# B166A.net
KiCad netlist of a schematic drawn in EAGLE
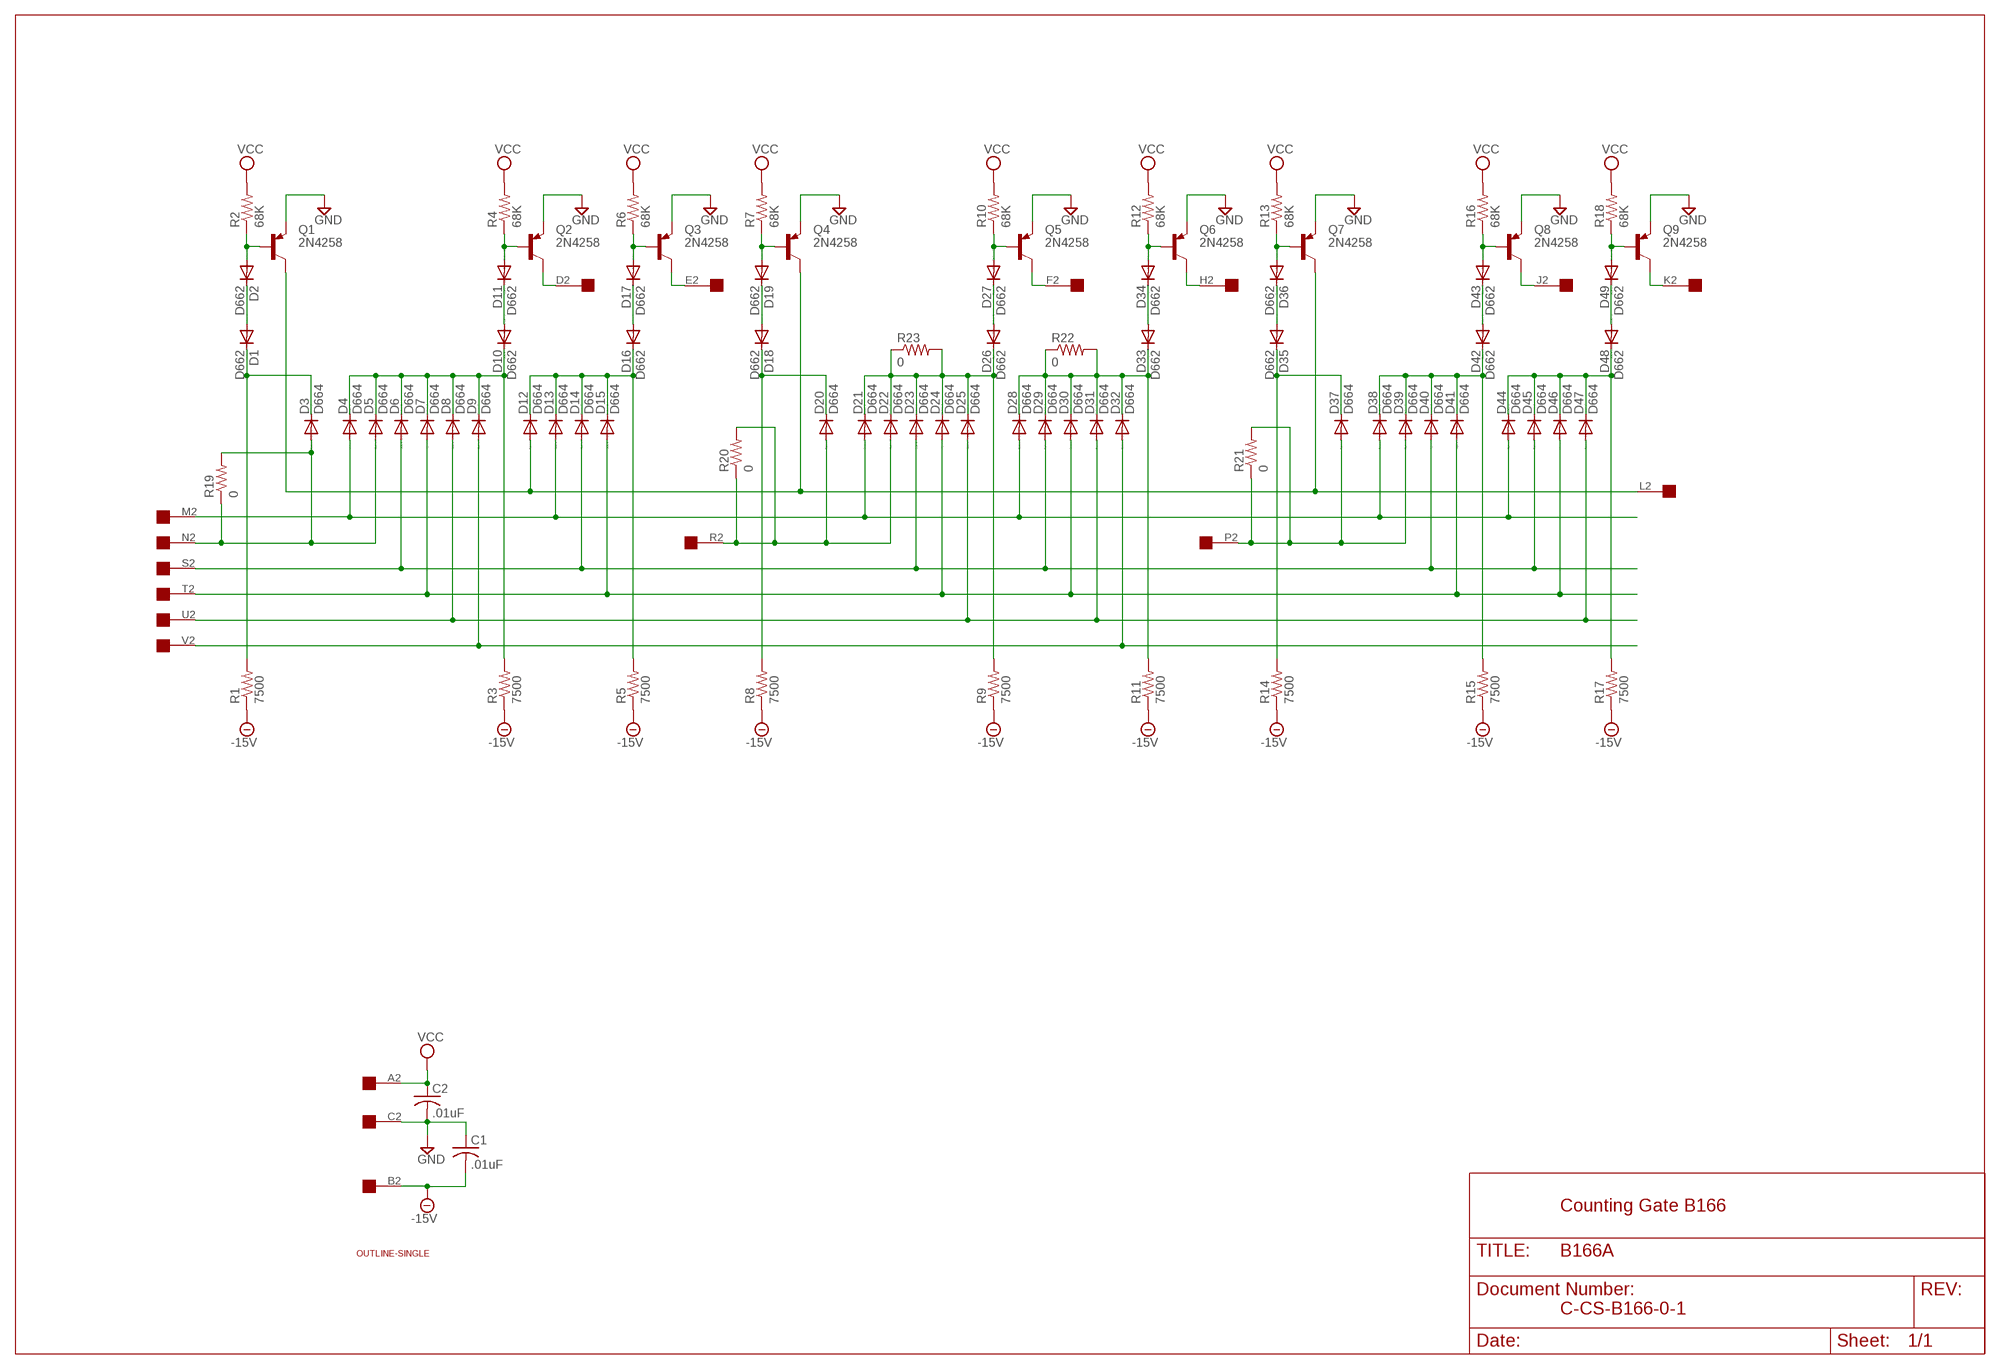
[diagram p0: schematic, sheet 1]

(export (version "E")
  (design (tool "Eeschema 10.0.6"))
  (components
    (comp (ref "C1")
      (value ".01uF")
      (footprint "eagle-import:C063-025X075")
      (libsource (lib "eagle-import") (part "C-US"))
    )
    (comp (ref "C2")
      (value ".01uF")
      (footprint "eagle-import:C063-025X075")
      (libsource (lib "eagle-import") (part "C-US"))
    )
    (comp (ref "D1")
      (value "D662")
      (footprint "eagle-import:DO35-10")
      (libsource (lib "eagle-import") (part "DIODE-DO35-10"))
    )
    (comp (ref "D2")
      (value "D662")
      (footprint "eagle-import:DO35-10")
      (libsource (lib "eagle-import") (part "DIODE-DO35-10"))
    )
    (comp (ref "D3")
      (value "D664")
      (footprint "eagle-import:DO35-10")
      (libsource (lib "eagle-import") (part "DIODE-DO35-10"))
    )
    (comp (ref "D4")
      (value "D664")
      (footprint "eagle-import:DO35-10")
      (libsource (lib "eagle-import") (part "DIODE-DO35-10"))
    )
    (comp (ref "D5")
      (value "D664")
      (footprint "eagle-import:DO35-10")
      (libsource (lib "eagle-import") (part "DIODE-DO35-10"))
    )
    (comp (ref "D6")
      (value "D664")
      (footprint "eagle-import:DO35-10")
      (libsource (lib "eagle-import") (part "DIODE-DO35-10"))
    )
    (comp (ref "D7")
      (value "D664")
      (footprint "eagle-import:DO35-10")
      (libsource (lib "eagle-import") (part "DIODE-DO35-10"))
    )
    (comp (ref "D8")
      (value "D664")
      (footprint "eagle-import:DO35-10")
      (libsource (lib "eagle-import") (part "DIODE-DO35-10"))
    )
    (comp (ref "D9")
      (value "D664")
      (footprint "eagle-import:DO35-10")
      (libsource (lib "eagle-import") (part "DIODE-DO35-10"))
    )
    (comp (ref "D10")
      (value "D662")
      (footprint "eagle-import:DO35-10")
      (libsource (lib "eagle-import") (part "DIODE-DO35-10"))
    )
    (comp (ref "D11")
      (value "D662")
      (footprint "eagle-import:DO35-10")
      (libsource (lib "eagle-import") (part "DIODE-DO35-10"))
    )
    (comp (ref "D12")
      (value "D664")
      (footprint "eagle-import:DO35-10")
      (libsource (lib "eagle-import") (part "DIODE-DO35-10"))
    )
    (comp (ref "D13")
      (value "D664")
      (footprint "eagle-import:DO35-10")
      (libsource (lib "eagle-import") (part "DIODE-DO35-10"))
    )
    (comp (ref "D14")
      (value "D664")
      (footprint "eagle-import:DO35-10")
      (libsource (lib "eagle-import") (part "DIODE-DO35-10"))
    )
    (comp (ref "D15")
      (value "D664")
      (footprint "eagle-import:DO35-10")
      (libsource (lib "eagle-import") (part "DIODE-DO35-10"))
    )
    (comp (ref "D16")
      (value "D662")
      (footprint "eagle-import:DO35-10")
      (libsource (lib "eagle-import") (part "DIODE-DO35-10"))
    )
    (comp (ref "D17")
      (value "D662")
      (footprint "eagle-import:DO35-10")
      (libsource (lib "eagle-import") (part "DIODE-DO35-10"))
    )
    (comp (ref "D18")
      (value "D662")
      (footprint "eagle-import:DO35-10")
      (libsource (lib "eagle-import") (part "DIODE-DO35-10"))
    )
    (comp (ref "D19")
      (value "D662")
      (footprint "eagle-import:DO35-10")
      (libsource (lib "eagle-import") (part "DIODE-DO35-10"))
    )
    (comp (ref "D20")
      (value "D664")
      (footprint "eagle-import:DO35-10")
      (libsource (lib "eagle-import") (part "DIODE-DO35-10"))
    )
    (comp (ref "D21")
      (value "D664")
      (footprint "eagle-import:DO35-10")
      (libsource (lib "eagle-import") (part "DIODE-DO35-10"))
    )
    (comp (ref "D22")
      (value "D664")
      (footprint "eagle-import:DO35-10")
      (libsource (lib "eagle-import") (part "DIODE-DO35-10"))
    )
    (comp (ref "D23")
      (value "D664")
      (footprint "eagle-import:DO35-10")
      (libsource (lib "eagle-import") (part "DIODE-DO35-10"))
    )
    (comp (ref "D24")
      (value "D664")
      (footprint "eagle-import:DO35-10")
      (libsource (lib "eagle-import") (part "DIODE-DO35-10"))
    )
    (comp (ref "D25")
      (value "D664")
      (footprint "eagle-import:DO35-10")
      (libsource (lib "eagle-import") (part "DIODE-DO35-10"))
    )
    (comp (ref "D26")
      (value "D662")
      (footprint "eagle-import:DO35-10")
      (libsource (lib "eagle-import") (part "DIODE-DO35-10"))
    )
    (comp (ref "D27")
      (value "D662")
      (footprint "eagle-import:DO35-10")
      (libsource (lib "eagle-import") (part "DIODE-DO35-10"))
    )
    (comp (ref "D28")
      (value "D664")
      (footprint "eagle-import:DO35-10")
      (libsource (lib "eagle-import") (part "DIODE-DO35-10"))
    )
    (comp (ref "D29")
      (value "D664")
      (footprint "eagle-import:DO35-10")
      (libsource (lib "eagle-import") (part "DIODE-DO35-10"))
    )
    (comp (ref "D30")
      (value "D664")
      (footprint "eagle-import:DO35-10")
      (libsource (lib "eagle-import") (part "DIODE-DO35-10"))
    )
    (comp (ref "D31")
      (value "D664")
      (footprint "eagle-import:DO35-10")
      (libsource (lib "eagle-import") (part "DIODE-DO35-10"))
    )
    (comp (ref "D32")
      (value "D664")
      (footprint "eagle-import:DO35-10")
      (libsource (lib "eagle-import") (part "DIODE-DO35-10"))
    )
    (comp (ref "D33")
      (value "D662")
      (footprint "eagle-import:DO35-10")
      (libsource (lib "eagle-import") (part "DIODE-DO35-10"))
    )
    (comp (ref "D34")
      (value "D662")
      (footprint "eagle-import:DO35-10")
      (libsource (lib "eagle-import") (part "DIODE-DO35-10"))
    )
    (comp (ref "D35")
      (value "D662")
      (footprint "eagle-import:DO35-10")
      (libsource (lib "eagle-import") (part "DIODE-DO35-10"))
    )
    (comp (ref "D36")
      (value "D662")
      (footprint "eagle-import:DO35-10")
      (libsource (lib "eagle-import") (part "DIODE-DO35-10"))
    )
    (comp (ref "D37")
      (value "D664")
      (footprint "eagle-import:DO35-10")
      (libsource (lib "eagle-import") (part "DIODE-DO35-10"))
    )
    (comp (ref "D38")
      (value "D664")
      (footprint "eagle-import:DO35-10")
      (libsource (lib "eagle-import") (part "DIODE-DO35-10"))
    )
    (comp (ref "D39")
      (value "D664")
      (footprint "eagle-import:DO35-10")
      (libsource (lib "eagle-import") (part "DIODE-DO35-10"))
    )
    (comp (ref "D40")
      (value "D664")
      (footprint "eagle-import:DO35-10")
      (libsource (lib "eagle-import") (part "DIODE-DO35-10"))
    )
    (comp (ref "D41")
      (value "D664")
      (footprint "eagle-import:DO35-10")
      (libsource (lib "eagle-import") (part "DIODE-DO35-10"))
    )
    (comp (ref "D42")
      (value "D662")
      (footprint "eagle-import:DO35-10")
      (libsource (lib "eagle-import") (part "DIODE-DO35-10"))
    )
    (comp (ref "D43")
      (value "D662")
      (footprint "eagle-import:DO35-10")
      (libsource (lib "eagle-import") (part "DIODE-DO35-10"))
    )
    (comp (ref "D44")
      (value "D664")
      (footprint "eagle-import:DO35-10")
      (libsource (lib "eagle-import") (part "DIODE-DO35-10"))
    )
    (comp (ref "D45")
      (value "D664")
      (footprint "eagle-import:DO35-10")
      (libsource (lib "eagle-import") (part "DIODE-DO35-10"))
    )
    (comp (ref "D46")
      (value "D664")
      (footprint "eagle-import:DO35-10")
      (libsource (lib "eagle-import") (part "DIODE-DO35-10"))
    )
    (comp (ref "D47")
      (value "D664")
      (footprint "eagle-import:DO35-10")
      (libsource (lib "eagle-import") (part "DIODE-DO35-10"))
    )
    (comp (ref "D48")
      (value "D662")
      (footprint "eagle-import:DO35-10")
      (libsource (lib "eagle-import") (part "DIODE-DO35-10"))
    )
    (comp (ref "D49")
      (value "D662")
      (footprint "eagle-import:DO35-10")
      (libsource (lib "eagle-import") (part "DIODE-DO35-10"))
    )
    (comp (ref "Q1")
      (value "2N4258")
      (footprint "eagle-import:TO5")
      (libsource (lib "eagle-import") (part "-PNP-TO5"))
    )
    (comp (ref "Q2")
      (value "2N4258")
      (footprint "eagle-import:TO5")
      (libsource (lib "eagle-import") (part "-PNP-TO5"))
    )
    (comp (ref "Q3")
      (value "2N4258")
      (footprint "eagle-import:TO5")
      (libsource (lib "eagle-import") (part "-PNP-TO5"))
    )
    (comp (ref "Q4")
      (value "2N4258")
      (footprint "eagle-import:TO5")
      (libsource (lib "eagle-import") (part "-PNP-TO5"))
    )
    (comp (ref "Q5")
      (value "2N4258")
      (footprint "eagle-import:TO5")
      (libsource (lib "eagle-import") (part "-PNP-TO5"))
    )
    (comp (ref "Q6")
      (value "2N4258")
      (footprint "eagle-import:TO5")
      (libsource (lib "eagle-import") (part "-PNP-TO5"))
    )
    (comp (ref "Q7")
      (value "2N4258")
      (footprint "eagle-import:TO5")
      (libsource (lib "eagle-import") (part "-PNP-TO5"))
    )
    (comp (ref "Q8")
      (value "2N4258")
      (footprint "eagle-import:TO5")
      (libsource (lib "eagle-import") (part "-PNP-TO5"))
    )
    (comp (ref "Q9")
      (value "2N4258")
      (footprint "eagle-import:TO5")
      (libsource (lib "eagle-import") (part "-PNP-TO5"))
    )
    (comp (ref "R1")
      (value "7500")
      (footprint "eagle-import:0207_10")
      (libsource (lib "eagle-import") (part "R-US_0207/10"))
    )
    (comp (ref "R2")
      (value "68K")
      (footprint "eagle-import:0207_10")
      (libsource (lib "eagle-import") (part "R-US_0207/10"))
    )
    (comp (ref "R3")
      (value "7500")
      (footprint "eagle-import:0207_10")
      (libsource (lib "eagle-import") (part "R-US_0207/10"))
    )
    (comp (ref "R4")
      (value "68K")
      (footprint "eagle-import:0207_10")
      (libsource (lib "eagle-import") (part "R-US_0207/10"))
    )
    (comp (ref "R5")
      (value "7500")
      (footprint "eagle-import:0207_10")
      (libsource (lib "eagle-import") (part "R-US_0207/10"))
    )
    (comp (ref "R6")
      (value "68K")
      (footprint "eagle-import:0207_10")
      (libsource (lib "eagle-import") (part "R-US_0207/10"))
    )
    (comp (ref "R7")
      (value "68K")
      (footprint "eagle-import:0207_10")
      (libsource (lib "eagle-import") (part "R-US_0207/10"))
    )
    (comp (ref "R8")
      (value "7500")
      (footprint "eagle-import:0207_10")
      (libsource (lib "eagle-import") (part "R-US_0207/10"))
    )
    (comp (ref "R9")
      (value "7500")
      (footprint "eagle-import:0207_10")
      (libsource (lib "eagle-import") (part "R-US_0207/10"))
    )
    (comp (ref "R10")
      (value "68K")
      (footprint "eagle-import:0207_10")
      (libsource (lib "eagle-import") (part "R-US_0207/10"))
    )
    (comp (ref "R11")
      (value "7500")
      (footprint "eagle-import:0207_10")
      (libsource (lib "eagle-import") (part "R-US_0207/10"))
    )
    (comp (ref "R12")
      (value "68K")
      (footprint "eagle-import:0207_10")
      (libsource (lib "eagle-import") (part "R-US_0207/10"))
    )
    (comp (ref "R13")
      (value "68K")
      (footprint "eagle-import:0207_10")
      (libsource (lib "eagle-import") (part "R-US_0207/10"))
    )
    (comp (ref "R14")
      (value "7500")
      (footprint "eagle-import:0207_10")
      (libsource (lib "eagle-import") (part "R-US_0207/10"))
    )
    (comp (ref "R15")
      (value "7500")
      (footprint "eagle-import:0207_10")
      (libsource (lib "eagle-import") (part "R-US_0207/10"))
    )
    (comp (ref "R16")
      (value "68K")
      (footprint "eagle-import:0207_10")
      (libsource (lib "eagle-import") (part "R-US_0207/10"))
    )
    (comp (ref "R17")
      (value "7500")
      (footprint "eagle-import:0207_10")
      (libsource (lib "eagle-import") (part "R-US_0207/10"))
    )
    (comp (ref "R18")
      (value "68K")
      (footprint "eagle-import:0207_10")
      (libsource (lib "eagle-import") (part "R-US_0207/10"))
    )
    (comp (ref "R19")
      (value "0")
      (footprint "eagle-import:0207_10")
      (libsource (lib "eagle-import") (part "R-US_0207/10"))
    )
    (comp (ref "R20")
      (value "0")
      (footprint "eagle-import:0207_10")
      (libsource (lib "eagle-import") (part "R-US_0207/10"))
    )
    (comp (ref "R21")
      (value "0")
      (footprint "eagle-import:0207_10")
      (libsource (lib "eagle-import") (part "R-US_0207/10"))
    )
    (comp (ref "R22")
      (value "0")
      (footprint "eagle-import:0207_10")
      (libsource (lib "eagle-import") (part "R-US_0207/10"))
    )
    (comp (ref "R23")
      (value "0")
      (footprint "eagle-import:0207_10")
      (libsource (lib "eagle-import") (part "R-US_0207/10"))
    )
    (comp (ref "U$1")
      (value "OUTLINE-SINGLE")
      (footprint "eagle-import:SINGLE")
      (libsource (lib "eagle-import") (part "OUTLINE-SINGLE"))
    )
    (comp (ref "U$2")
      (value "EDGE-1")
      (footprint "eagle-import:EDGE-CON1")
      (libsource (lib "eagle-import") (part "EDGE-1"))
    )
  )
  (nets
    (net (code "1") (name "-15V") (class "Default")
      (node (ref "C1") (pin "2") (pinfunction "2_2") (pintype "passive"))
      (node (ref "R1") (pin "1") (pinfunction "1_1") (pintype "passive"))
      (node (ref "R11") (pin "1") (pinfunction "1_1") (pintype "passive"))
      (node (ref "R14") (pin "1") (pinfunction "1_1") (pintype "passive"))
      (node (ref "R15") (pin "1") (pinfunction "1_1") (pintype "passive"))
      (node (ref "R17") (pin "1") (pinfunction "1_1") (pintype "passive"))
      (node (ref "R3") (pin "1") (pinfunction "1_1") (pintype "passive"))
      (node (ref "R5") (pin "1") (pinfunction "1_1") (pintype "passive"))
      (node (ref "R8") (pin "1") (pinfunction "1_1") (pintype "passive"))
      (node (ref "R9") (pin "1") (pinfunction "1_1") (pintype "passive"))
      (node (ref "U$2") (pin "B2") (pinfunction "1_B2") (pintype "bidirectional"))
    )
    (net (code "2") (name "GND") (class "Default")
      (node (ref "C1") (pin "1") (pinfunction "1_1") (pintype "passive"))
      (node (ref "C2") (pin "2") (pinfunction "2_2") (pintype "passive"))
      (node (ref "Q1") (pin "1") (pinfunction "E_1") (pintype "passive"))
      (node (ref "Q2") (pin "1") (pinfunction "E_1") (pintype "passive"))
      (node (ref "Q3") (pin "1") (pinfunction "E_1") (pintype "passive"))
      (node (ref "Q4") (pin "1") (pinfunction "E_1") (pintype "passive"))
      (node (ref "Q5") (pin "1") (pinfunction "E_1") (pintype "passive"))
      (node (ref "Q6") (pin "1") (pinfunction "E_1") (pintype "passive"))
      (node (ref "Q7") (pin "1") (pinfunction "E_1") (pintype "passive"))
      (node (ref "Q8") (pin "1") (pinfunction "E_1") (pintype "passive"))
      (node (ref "Q9") (pin "1") (pinfunction "E_1") (pintype "passive"))
      (node (ref "U$2") (pin "C2") (pinfunction "1_C2") (pintype "bidirectional"))
    )
    (net (code "3") (name "Net-(D1-PadA)") (class "Default")
      (node (ref "D1") (pin "A") (pinfunction "A_A") (pintype "passive"))
      (node (ref "D2") (pin "C") (pinfunction "C_C") (pintype "passive"))
    )
    (net (code "4") (name "Net-(D1-PadC)") (class "Default")
      (node (ref "D1") (pin "C") (pinfunction "C_C") (pintype "passive"))
      (node (ref "D3") (pin "C") (pinfunction "C_C") (pintype "passive"))
      (node (ref "R1") (pin "2") (pinfunction "2_2") (pintype "passive"))
    )
    (net (code "5") (name "Net-(D10-PadA)") (class "Default")
      (node (ref "D10") (pin "A") (pinfunction "A_A") (pintype "passive"))
      (node (ref "D11") (pin "C") (pinfunction "C_C") (pintype "passive"))
    )
    (net (code "6") (name "Net-(D10-PadC)") (class "Default")
      (node (ref "D10") (pin "C") (pinfunction "C_C") (pintype "passive"))
      (node (ref "D4") (pin "C") (pinfunction "C_C") (pintype "passive"))
      (node (ref "D5") (pin "C") (pinfunction "C_C") (pintype "passive"))
      (node (ref "D6") (pin "C") (pinfunction "C_C") (pintype "passive"))
      (node (ref "D7") (pin "C") (pinfunction "C_C") (pintype "passive"))
      (node (ref "D8") (pin "C") (pinfunction "C_C") (pintype "passive"))
      (node (ref "D9") (pin "C") (pinfunction "C_C") (pintype "passive"))
      (node (ref "R3") (pin "2") (pinfunction "2_2") (pintype "passive"))
    )
    (net (code "7") (name "Net-(D12-PadC)") (class "Default")
      (node (ref "D12") (pin "C") (pinfunction "C_C") (pintype "passive"))
      (node (ref "D13") (pin "C") (pinfunction "C_C") (pintype "passive"))
      (node (ref "D14") (pin "C") (pinfunction "C_C") (pintype "passive"))
      (node (ref "D15") (pin "C") (pinfunction "C_C") (pintype "passive"))
      (node (ref "D16") (pin "C") (pinfunction "C_C") (pintype "passive"))
      (node (ref "R5") (pin "2") (pinfunction "2_2") (pintype "passive"))
    )
    (net (code "8") (name "Net-(D16-PadA)") (class "Default")
      (node (ref "D16") (pin "A") (pinfunction "A_A") (pintype "passive"))
      (node (ref "D17") (pin "C") (pinfunction "C_C") (pintype "passive"))
    )
    (net (code "9") (name "Net-(D18-PadA)") (class "Default")
      (node (ref "D18") (pin "A") (pinfunction "A_A") (pintype "passive"))
      (node (ref "D19") (pin "C") (pinfunction "C_C") (pintype "passive"))
    )
    (net (code "10") (name "Net-(D18-PadC)") (class "Default")
      (node (ref "D18") (pin "C") (pinfunction "C_C") (pintype "passive"))
      (node (ref "D20") (pin "C") (pinfunction "C_C") (pintype "passive"))
      (node (ref "R8") (pin "2") (pinfunction "2_2") (pintype "passive"))
    )
    (net (code "11") (name "Net-(D21-PadC)") (class "Default")
      (node (ref "D21") (pin "C") (pinfunction "C_C") (pintype "passive"))
      (node (ref "D22") (pin "C") (pinfunction "C_C") (pintype "passive"))
      (node (ref "D23") (pin "C") (pinfunction "C_C") (pintype "passive"))
      (node (ref "D24") (pin "C") (pinfunction "C_C") (pintype "passive"))
      (node (ref "D25") (pin "C") (pinfunction "C_C") (pintype "passive"))
      (node (ref "D26") (pin "C") (pinfunction "C_C") (pintype "passive"))
      (node (ref "R23") (pin "1") (pinfunction "1_1") (pintype "passive"))
      (node (ref "R23") (pin "2") (pinfunction "2_2") (pintype "passive"))
      (node (ref "R9") (pin "2") (pinfunction "2_2") (pintype "passive"))
    )
    (net (code "12") (name "Net-(D26-PadA)") (class "Default")
      (node (ref "D26") (pin "A") (pinfunction "A_A") (pintype "passive"))
      (node (ref "D27") (pin "C") (pinfunction "C_C") (pintype "passive"))
    )
    (net (code "13") (name "Net-(D28-PadC)") (class "Default")
      (node (ref "D28") (pin "C") (pinfunction "C_C") (pintype "passive"))
      (node (ref "D29") (pin "C") (pinfunction "C_C") (pintype "passive"))
      (node (ref "D30") (pin "C") (pinfunction "C_C") (pintype "passive"))
      (node (ref "D31") (pin "C") (pinfunction "C_C") (pintype "passive"))
      (node (ref "D32") (pin "C") (pinfunction "C_C") (pintype "passive"))
      (node (ref "D33") (pin "C") (pinfunction "C_C") (pintype "passive"))
      (node (ref "R11") (pin "2") (pinfunction "2_2") (pintype "passive"))
      (node (ref "R22") (pin "1") (pinfunction "1_1") (pintype "passive"))
      (node (ref "R22") (pin "2") (pinfunction "2_2") (pintype "passive"))
    )
    (net (code "14") (name "Net-(D33-PadA)") (class "Default")
      (node (ref "D33") (pin "A") (pinfunction "A_A") (pintype "passive"))
      (node (ref "D34") (pin "C") (pinfunction "C_C") (pintype "passive"))
    )
    (net (code "15") (name "Net-(D35-PadA)") (class "Default")
      (node (ref "D35") (pin "A") (pinfunction "A_A") (pintype "passive"))
      (node (ref "D36") (pin "C") (pinfunction "C_C") (pintype "passive"))
    )
    (net (code "16") (name "Net-(D35-PadC)") (class "Default")
      (node (ref "D35") (pin "C") (pinfunction "C_C") (pintype "passive"))
      (node (ref "D37") (pin "C") (pinfunction "C_C") (pintype "passive"))
      (node (ref "R14") (pin "2") (pinfunction "2_2") (pintype "passive"))
    )
    (net (code "17") (name "Net-(D38-PadC)") (class "Default")
      (node (ref "D38") (pin "C") (pinfunction "C_C") (pintype "passive"))
      (node (ref "D39") (pin "C") (pinfunction "C_C") (pintype "passive"))
      (node (ref "D40") (pin "C") (pinfunction "C_C") (pintype "passive"))
      (node (ref "D41") (pin "C") (pinfunction "C_C") (pintype "passive"))
      (node (ref "D42") (pin "C") (pinfunction "C_C") (pintype "passive"))
      (node (ref "R15") (pin "2") (pinfunction "2_2") (pintype "passive"))
    )
    (net (code "18") (name "Net-(D42-PadA)") (class "Default")
      (node (ref "D42") (pin "A") (pinfunction "A_A") (pintype "passive"))
      (node (ref "D43") (pin "C") (pinfunction "C_C") (pintype "passive"))
    )
    (net (code "19") (name "Net-(D44-PadC)") (class "Default")
      (node (ref "D44") (pin "C") (pinfunction "C_C") (pintype "passive"))
      (node (ref "D45") (pin "C") (pinfunction "C_C") (pintype "passive"))
      (node (ref "D46") (pin "C") (pinfunction "C_C") (pintype "passive"))
      (node (ref "D47") (pin "C") (pinfunction "C_C") (pintype "passive"))
      (node (ref "D48") (pin "C") (pinfunction "C_C") (pintype "passive"))
      (node (ref "R17") (pin "2") (pinfunction "2_2") (pintype "passive"))
    )
    (net (code "20") (name "Net-(D48-PadA)") (class "Default")
      (node (ref "D48") (pin "A") (pinfunction "A_A") (pintype "passive"))
      (node (ref "D49") (pin "C") (pinfunction "C_C") (pintype "passive"))
    )
    (net (code "21") (name "Net-(Q1-B)") (class "Default")
      (node (ref "D2") (pin "A") (pinfunction "A_A") (pintype "passive"))
      (node (ref "Q1") (pin "2") (pinfunction "B_2") (pintype "passive"))
      (node (ref "R2") (pin "1") (pinfunction "1_1") (pintype "passive"))
    )
    (net (code "22") (name "Net-(Q1-C)") (class "Default")
      (node (ref "D12") (pin "A") (pinfunction "A_A") (pintype "passive"))
      (node (ref "Q1") (pin "3") (pinfunction "C_3") (pintype "passive"))
      (node (ref "Q4") (pin "3") (pinfunction "C_3") (pintype "passive"))
      (node (ref "Q7") (pin "3") (pinfunction "C_3") (pintype "passive"))
      (node (ref "U$2") (pin "L2") (pinfunction "1_L2") (pintype "bidirectional"))
    )
    (net (code "23") (name "Net-(Q2-B)") (class "Default")
      (node (ref "D11") (pin "A") (pinfunction "A_A") (pintype "passive"))
      (node (ref "Q2") (pin "2") (pinfunction "B_2") (pintype "passive"))
      (node (ref "R4") (pin "1") (pinfunction "1_1") (pintype "passive"))
    )
    (net (code "24") (name "Net-(Q2-C)") (class "Default")
      (node (ref "Q2") (pin "3") (pinfunction "C_3") (pintype "passive"))
      (node (ref "U$2") (pin "D2") (pinfunction "1_D2") (pintype "bidirectional"))
    )
    (net (code "25") (name "Net-(Q3-B)") (class "Default")
      (node (ref "D17") (pin "A") (pinfunction "A_A") (pintype "passive"))
      (node (ref "Q3") (pin "2") (pinfunction "B_2") (pintype "passive"))
      (node (ref "R6") (pin "1") (pinfunction "1_1") (pintype "passive"))
    )
    (net (code "26") (name "Net-(Q3-C)") (class "Default")
      (node (ref "Q3") (pin "3") (pinfunction "C_3") (pintype "passive"))
      (node (ref "U$2") (pin "E2") (pinfunction "1_E2") (pintype "bidirectional"))
    )
    (net (code "27") (name "Net-(Q4-B)") (class "Default")
      (node (ref "D19") (pin "A") (pinfunction "A_A") (pintype "passive"))
      (node (ref "Q4") (pin "2") (pinfunction "B_2") (pintype "passive"))
      (node (ref "R7") (pin "1") (pinfunction "1_1") (pintype "passive"))
    )
    (net (code "28") (name "Net-(Q5-B)") (class "Default")
      (node (ref "D27") (pin "A") (pinfunction "A_A") (pintype "passive"))
      (node (ref "Q5") (pin "2") (pinfunction "B_2") (pintype "passive"))
      (node (ref "R10") (pin "1") (pinfunction "1_1") (pintype "passive"))
    )
    (net (code "29") (name "Net-(Q5-C)") (class "Default")
      (node (ref "Q5") (pin "3") (pinfunction "C_3") (pintype "passive"))
      (node (ref "U$2") (pin "F2") (pinfunction "1_F2") (pintype "bidirectional"))
    )
    (net (code "30") (name "Net-(Q6-B)") (class "Default")
      (node (ref "D34") (pin "A") (pinfunction "A_A") (pintype "passive"))
      (node (ref "Q6") (pin "2") (pinfunction "B_2") (pintype "passive"))
      (node (ref "R12") (pin "1") (pinfunction "1_1") (pintype "passive"))
    )
    (net (code "31") (name "Net-(Q6-C)") (class "Default")
      (node (ref "Q6") (pin "3") (pinfunction "C_3") (pintype "passive"))
      (node (ref "U$2") (pin "H2") (pinfunction "1_H2") (pintype "bidirectional"))
    )
    (net (code "32") (name "Net-(Q7-B)") (class "Default")
      (node (ref "D36") (pin "A") (pinfunction "A_A") (pintype "passive"))
      (node (ref "Q7") (pin "2") (pinfunction "B_2") (pintype "passive"))
      (node (ref "R13") (pin "1") (pinfunction "1_1") (pintype "passive"))
    )
    (net (code "33") (name "Net-(Q8-B)") (class "Default")
      (node (ref "D43") (pin "A") (pinfunction "A_A") (pintype "passive"))
      (node (ref "Q8") (pin "2") (pinfunction "B_2") (pintype "passive"))
      (node (ref "R16") (pin "1") (pinfunction "1_1") (pintype "passive"))
    )
    (net (code "34") (name "Net-(Q8-C)") (class "Default")
      (node (ref "Q8") (pin "3") (pinfunction "C_3") (pintype "passive"))
      (node (ref "U$2") (pin "J2") (pinfunction "1_J2") (pintype "bidirectional"))
    )
    (net (code "35") (name "Net-(Q9-B)") (class "Default")
      (node (ref "D49") (pin "A") (pinfunction "A_A") (pintype "passive"))
      (node (ref "Q9") (pin "2") (pinfunction "B_2") (pintype "passive"))
      (node (ref "R18") (pin "1") (pinfunction "1_1") (pintype "passive"))
    )
    (net (code "36") (name "Net-(Q9-C)") (class "Default")
      (node (ref "Q9") (pin "3") (pinfunction "C_3") (pintype "passive"))
      (node (ref "U$2") (pin "K2") (pinfunction "1_K2") (pintype "bidirectional"))
    )
    (net (code "37") (name "Net-(U$2K-1)") (class "Default")
      (node (ref "D13") (pin "A") (pinfunction "A_A") (pintype "passive"))
      (node (ref "D21") (pin "A") (pinfunction "A_A") (pintype "passive"))
      (node (ref "D28") (pin "A") (pinfunction "A_A") (pintype "passive"))
      (node (ref "D38") (pin "A") (pinfunction "A_A") (pintype "passive"))
      (node (ref "D4") (pin "A") (pinfunction "A_A") (pintype "passive"))
      (node (ref "D44") (pin "A") (pinfunction "A_A") (pintype "passive"))
      (node (ref "U$2") (pin "M2") (pinfunction "1_M2") (pintype "bidirectional"))
    )
    (net (code "38") (name "Net-(U$2L-1)") (class "Default")
      (node (ref "D3") (pin "A") (pinfunction "A_A") (pintype "passive"))
      (node (ref "D5") (pin "A") (pinfunction "A_A") (pintype "passive"))
      (node (ref "R19") (pin "1") (pinfunction "1_1") (pintype "passive"))
      (node (ref "R19") (pin "2") (pinfunction "2_2") (pintype "passive"))
      (node (ref "U$2") (pin "N2") (pinfunction "1_N2") (pintype "bidirectional"))
    )
    (net (code "39") (name "Net-(U$2M-1)") (class "Default")
      (node (ref "D37") (pin "A") (pinfunction "A_A") (pintype "passive"))
      (node (ref "D39") (pin "A") (pinfunction "A_A") (pintype "passive"))
      (node (ref "R21") (pin "1") (pinfunction "1_1") (pintype "passive"))
      (node (ref "R21") (pin "2") (pinfunction "2_2") (pintype "passive"))
      (node (ref "U$2") (pin "P2") (pinfunction "1_P2") (pintype "bidirectional"))
    )
    (net (code "40") (name "Net-(U$2N-1)") (class "Default")
      (node (ref "D20") (pin "A") (pinfunction "A_A") (pintype "passive"))
      (node (ref "D22") (pin "A") (pinfunction "A_A") (pintype "passive"))
      (node (ref "R20") (pin "1") (pinfunction "1_1") (pintype "passive"))
      (node (ref "R20") (pin "2") (pinfunction "2_2") (pintype "passive"))
      (node (ref "U$2") (pin "R2") (pinfunction "1_R2") (pintype "bidirectional"))
    )
    (net (code "41") (name "Net-(U$2O-1)") (class "Default")
      (node (ref "D14") (pin "A") (pinfunction "A_A") (pintype "passive"))
      (node (ref "D23") (pin "A") (pinfunction "A_A") (pintype "passive"))
      (node (ref "D29") (pin "A") (pinfunction "A_A") (pintype "passive"))
      (node (ref "D40") (pin "A") (pinfunction "A_A") (pintype "passive"))
      (node (ref "D45") (pin "A") (pinfunction "A_A") (pintype "passive"))
      (node (ref "D6") (pin "A") (pinfunction "A_A") (pintype "passive"))
      (node (ref "U$2") (pin "S2") (pinfunction "1_S2") (pintype "bidirectional"))
    )
    (net (code "42") (name "Net-(U$2P-1)") (class "Default")
      (node (ref "D15") (pin "A") (pinfunction "A_A") (pintype "passive"))
      (node (ref "D24") (pin "A") (pinfunction "A_A") (pintype "passive"))
      (node (ref "D30") (pin "A") (pinfunction "A_A") (pintype "passive"))
      (node (ref "D41") (pin "A") (pinfunction "A_A") (pintype "passive"))
      (node (ref "D46") (pin "A") (pinfunction "A_A") (pintype "passive"))
      (node (ref "D7") (pin "A") (pinfunction "A_A") (pintype "passive"))
      (node (ref "U$2") (pin "T2") (pinfunction "1_T2") (pintype "bidirectional"))
    )
    (net (code "43") (name "Net-(U$2Q-1)") (class "Default")
      (node (ref "D25") (pin "A") (pinfunction "A_A") (pintype "passive"))
      (node (ref "D31") (pin "A") (pinfunction "A_A") (pintype "passive"))
      (node (ref "D47") (pin "A") (pinfunction "A_A") (pintype "passive"))
      (node (ref "D8") (pin "A") (pinfunction "A_A") (pintype "passive"))
      (node (ref "U$2") (pin "U2") (pinfunction "1_U2") (pintype "bidirectional"))
    )
    (net (code "44") (name "Net-(U$2R-1)") (class "Default")
      (node (ref "D32") (pin "A") (pinfunction "A_A") (pintype "passive"))
      (node (ref "D9") (pin "A") (pinfunction "A_A") (pintype "passive"))
      (node (ref "U$2") (pin "V2") (pinfunction "1_V2") (pintype "bidirectional"))
    )
    (net (code "45") (name "VCC") (class "Default")
      (node (ref "C2") (pin "1") (pinfunction "1_1") (pintype "passive"))
      (node (ref "R10") (pin "2") (pinfunction "2_2") (pintype "passive"))
      (node (ref "R12") (pin "2") (pinfunction "2_2") (pintype "passive"))
      (node (ref "R13") (pin "2") (pinfunction "2_2") (pintype "passive"))
      (node (ref "R16") (pin "2") (pinfunction "2_2") (pintype "passive"))
      (node (ref "R18") (pin "2") (pinfunction "2_2") (pintype "passive"))
      (node (ref "R2") (pin "2") (pinfunction "2_2") (pintype "passive"))
      (node (ref "R4") (pin "2") (pinfunction "2_2") (pintype "passive"))
      (node (ref "R6") (pin "2") (pinfunction "2_2") (pintype "passive"))
      (node (ref "R7") (pin "2") (pinfunction "2_2") (pintype "passive"))
      (node (ref "U$2") (pin "A2") (pinfunction "1_A2") (pintype "bidirectional"))
    )
  )
)
